# Bite_Force_System_Schematic.net
KiCad netlist of a schematic drawn in Altium Designer
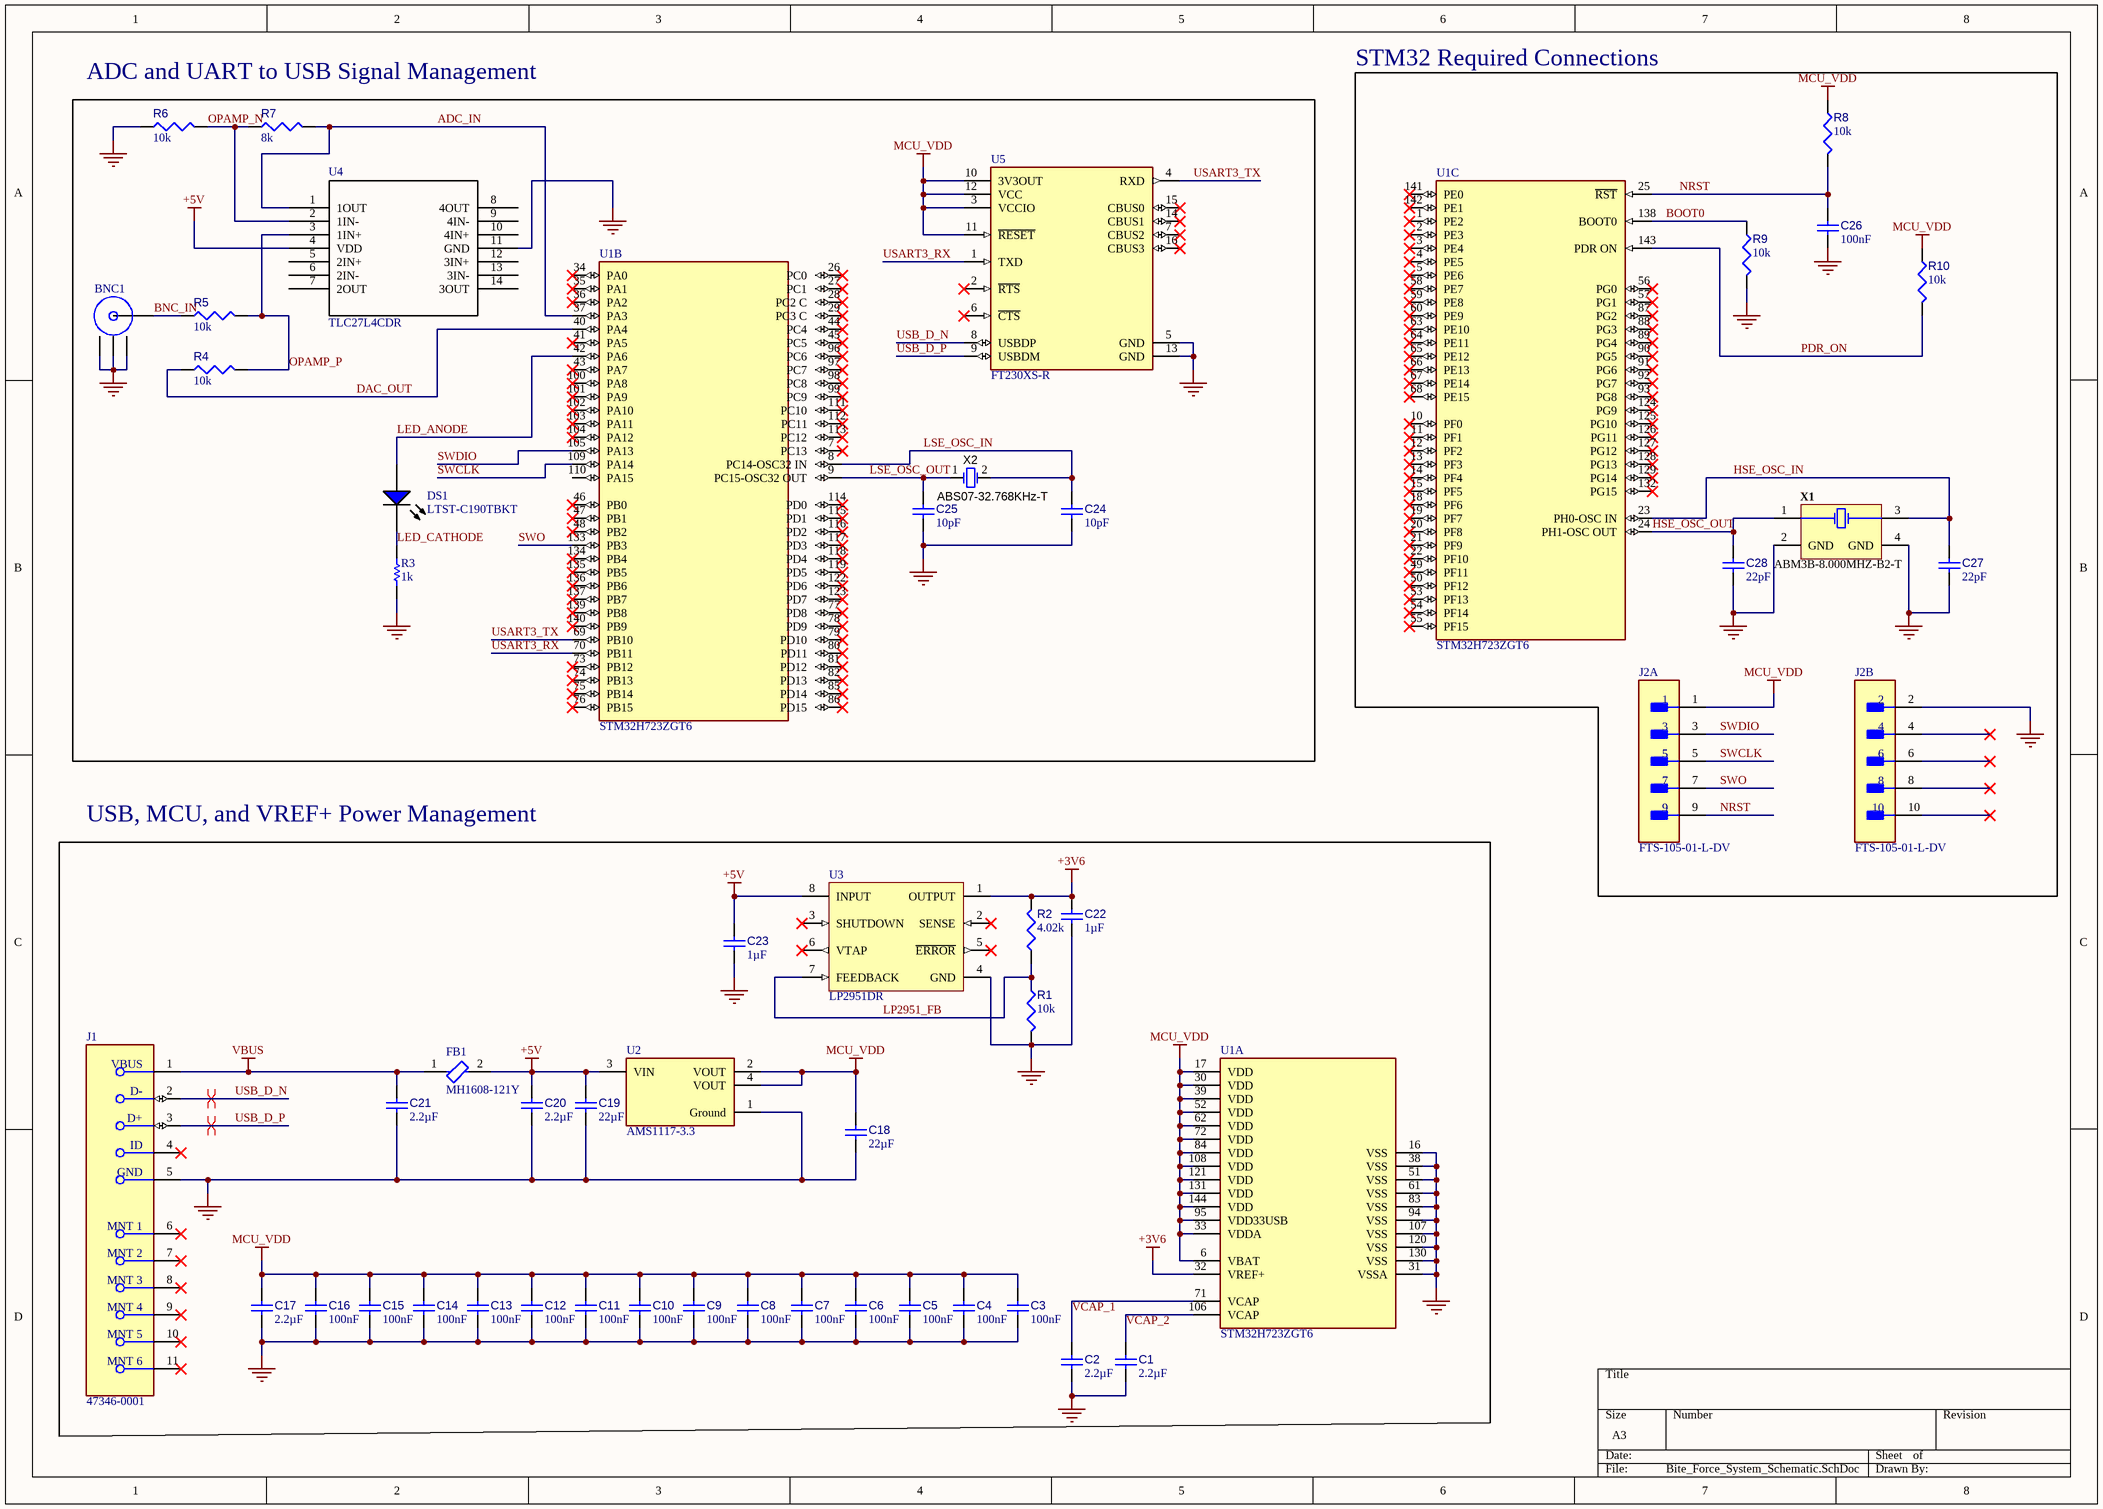
[diagram p0: Bite_Force_System_Schematic.SchDoc]

(export (version "E")
  (design (tool "Eeschema 10.0.6"))
  (components
    (comp (ref "BNC1")
      (value "KH-BNC75-3511")
      (footprint "KH-BNC75-3511-Footprint-1")
      (description "1 Inner Hole BNC Board-End Elbow 3GHz -55℃~+155℃ 75Ω 9.5mm Plugin Coaxial Connectors (RF) ROHS")
      (libsource (lib "Hayden Cao") (part "KH-BNC75-3511-Symbol-1"))
    )
    (comp (ref "C1")
      (value "2.2µF")
      (footprint "CAPC0402(1005)60_L")
      (description "Chip Capacitor, 2,2µF +/-20%, 10V, 0402, Thickness 0.6 mm")
      (fields (field (name "TOLERANCE") "10%") (field (name "Comment") "Capacitor 2,2µF +/-20% 10V 0402"))
      (libsource (lib "Hayden Cao") (part "CAP-NP-2"))
    )
    (comp (ref "C2")
      (value "2.2µF")
      (footprint "CAPC0402(1005)60_L")
      (description "Chip Capacitor, 2,2µF +/-20%, 10V, 0402, Thickness 0.6 mm")
      (fields (field (name "TOLERANCE") "10%") (field (name "Comment") "Capacitor 2,2µF +/-20% 10V 0402"))
      (libsource (lib "Hayden Cao") (part "CAP-NP-2"))
    )
    (comp (ref "C3")
      (value "100nF")
      (footprint "CAPC0402(1005)60_L")
      (description "Chip Capacitor, 100nF +/-20%, 25V, 0402, Thickness 0.6 mm")
      (fields (field (name "TOLERANCE") "10%") (field (name "Comment") "Capacitor 100nF +/-20% 25V 0402"))
      (libsource (lib "Hayden Cao") (part "CAP-NP-2"))
    )
    (comp (ref "C4")
      (value "100nF")
      (footprint "CAPC0402(1005)60_L")
      (description "Chip Capacitor, 100nF +/-20%, 25V, 0402, Thickness 0.6 mm")
      (fields (field (name "TOLERANCE") "10%") (field (name "Comment") "Capacitor 100nF +/-20% 25V 0402"))
      (libsource (lib "Hayden Cao") (part "CAP-NP-2"))
    )
    (comp (ref "C5")
      (value "100nF")
      (footprint "CAPC0402(1005)60_L")
      (description "Chip Capacitor, 100nF +/-20%, 25V, 0402, Thickness 0.6 mm")
      (fields (field (name "TOLERANCE") "10%") (field (name "Comment") "Capacitor 100nF +/-20% 25V 0402"))
      (libsource (lib "Hayden Cao") (part "CAP-NP-2"))
    )
    (comp (ref "C6")
      (value "100nF")
      (footprint "CAPC0402(1005)60_L")
      (description "Chip Capacitor, 100nF +/-20%, 25V, 0402, Thickness 0.6 mm")
      (fields (field (name "TOLERANCE") "10%") (field (name "Comment") "Capacitor 100nF +/-20% 25V 0402"))
      (libsource (lib "Hayden Cao") (part "CAP-NP-2"))
    )
    (comp (ref "C7")
      (value "100nF")
      (footprint "CAPC0402(1005)60_L")
      (description "Chip Capacitor, 100nF +/-20%, 25V, 0402, Thickness 0.6 mm")
      (fields (field (name "TOLERANCE") "10%") (field (name "Comment") "Capacitor 100nF +/-20% 25V 0402"))
      (libsource (lib "Hayden Cao") (part "CAP-NP-2"))
    )
    (comp (ref "C8")
      (value "100nF")
      (footprint "CAPC0402(1005)60_L")
      (description "Chip Capacitor, 100nF +/-20%, 25V, 0402, Thickness 0.6 mm")
      (fields (field (name "TOLERANCE") "10%") (field (name "Comment") "Capacitor 100nF +/-20% 25V 0402"))
      (libsource (lib "Hayden Cao") (part "CAP-NP-2"))
    )
    (comp (ref "C9")
      (value "100nF")
      (footprint "CAPC0402(1005)60_L")
      (description "Chip Capacitor, 100nF +/-20%, 25V, 0402, Thickness 0.6 mm")
      (fields (field (name "TOLERANCE") "10%") (field (name "Comment") "Capacitor 100nF +/-20% 25V 0402"))
      (libsource (lib "Hayden Cao") (part "CAP-NP-2"))
    )
    (comp (ref "C10")
      (value "100nF")
      (footprint "CAPC0402(1005)60_L")
      (description "Chip Capacitor, 100nF +/-20%, 25V, 0402, Thickness 0.6 mm")
      (fields (field (name "TOLERANCE") "10%") (field (name "Comment") "Capacitor 100nF +/-20% 25V 0402"))
      (libsource (lib "Hayden Cao") (part "CAP-NP-2"))
    )
    (comp (ref "C11")
      (value "100nF")
      (footprint "CAPC0402(1005)60_L")
      (description "Chip Capacitor, 100nF +/-20%, 25V, 0402, Thickness 0.6 mm")
      (fields (field (name "TOLERANCE") "10%") (field (name "Comment") "Capacitor 100nF +/-20% 25V 0402"))
      (libsource (lib "Hayden Cao") (part "CAP-NP-2"))
    )
    (comp (ref "C12")
      (value "100nF")
      (footprint "CAPC0402(1005)60_L")
      (description "Chip Capacitor, 100nF +/-20%, 25V, 0402, Thickness 0.6 mm")
      (fields (field (name "TOLERANCE") "10%") (field (name "Comment") "Capacitor 100nF +/-20% 25V 0402"))
      (libsource (lib "Hayden Cao") (part "CAP-NP-2"))
    )
    (comp (ref "C13")
      (value "100nF")
      (footprint "CAPC0402(1005)60_L")
      (description "Chip Capacitor, 100nF +/-20%, 25V, 0402, Thickness 0.6 mm")
      (fields (field (name "TOLERANCE") "10%") (field (name "Comment") "Capacitor 100nF +/-20% 25V 0402"))
      (libsource (lib "Hayden Cao") (part "CAP-NP-2"))
    )
    (comp (ref "C14")
      (value "100nF")
      (footprint "CAPC0402(1005)60_L")
      (description "Chip Capacitor, 100nF +/-20%, 25V, 0402, Thickness 0.6 mm")
      (fields (field (name "TOLERANCE") "10%") (field (name "Comment") "Capacitor 100nF +/-20% 25V 0402"))
      (libsource (lib "Hayden Cao") (part "CAP-NP-2"))
    )
    (comp (ref "C15")
      (value "100nF")
      (footprint "CAPC0402(1005)60_L")
      (description "Chip Capacitor, 100nF +/-20%, 25V, 0402, Thickness 0.6 mm")
      (fields (field (name "TOLERANCE") "10%") (field (name "Comment") "Capacitor 100nF +/-20% 25V 0402"))
      (libsource (lib "Hayden Cao") (part "CAP-NP-2"))
    )
    (comp (ref "C16")
      (value "100nF")
      (footprint "CAPC0402(1005)60_L")
      (description "Chip Capacitor, 100nF +/-20%, 25V, 0402, Thickness 0.6 mm")
      (fields (field (name "TOLERANCE") "10%") (field (name "Comment") "Capacitor 100nF +/-20% 25V 0402"))
      (libsource (lib "Hayden Cao") (part "CAP-NP-2"))
    )
    (comp (ref "C17")
      (value "2.2µF")
      (footprint "CAPC0402(1005)60_L")
      (description "Chip Capacitor, 2,2µF +/-20%, 10V, 0402, Thickness 0.6 mm")
      (fields (field (name "TOLERANCE") "10%") (field (name "Comment") "Capacitor 2,2µF +/-20% 10V 0402"))
      (libsource (lib "Hayden Cao") (part "CAP-NP-2"))
    )
    (comp (ref "C18")
      (value "22µF")
      (footprint "CAPC0805(2012)145_L")
      (description "Chip Capacitor, 22µF +/-40%, 16V, 0805, Thickness 1.45 mm")
      (fields (field (name "TOLERANCE") "5%") (field (name "Comment") "Capacitor 22µF +/-40% 16V 0805"))
      (libsource (lib "Hayden Cao") (part "CAP-NP-2"))
    )
    (comp (ref "C19")
      (value "22µF")
      (footprint "CAPC0805(2012)145_L")
      (description "Chip Capacitor, 22µF +/-40%, 16V, 0805, Thickness 1.45 mm")
      (fields (field (name "TOLERANCE") "5%") (field (name "Comment") "Capacitor 22µF +/-40% 16V 0805"))
      (libsource (lib "Hayden Cao") (part "CAP-NP-2"))
    )
    (comp (ref "C20")
      (value "2.2µF")
      (footprint "CAPC0402(1005)60_L")
      (description "Chip Capacitor, 2,2µF +/-20%, 10V, 0402, Thickness 0.6 mm")
      (fields (field (name "TOLERANCE") "10%") (field (name "Comment") "Capacitor 2,2µF +/-20% 10V 0402"))
      (libsource (lib "Hayden Cao") (part "CAP-NP-2"))
    )
    (comp (ref "C21")
      (value "2.2µF")
      (footprint "CAPC0402(1005)60_L")
      (description "Chip Capacitor, 2,2µF +/-20%, 10V, 0402, Thickness 0.6 mm")
      (fields (field (name "TOLERANCE") "10%") (field (name "Comment") "Capacitor 2,2µF +/-20% 10V 0402"))
      (libsource (lib "Hayden Cao") (part "CAP-NP-2"))
    )
    (comp (ref "C22")
      (value "1µF")
      (footprint "CAPC1608X90X35ML15T15")
      (description "Chip Capacitor, 1 uF, +/- 10%, 16 V, 0603 (1608 Metric)")
      (fields (field (name "TOLERANCE") "10%") (field (name "Comment") "Capacitor 1uF +/- 10% 16V 0603"))
      (libsource (lib "Hayden Cao") (part "CAP-NP-2"))
    )
    (comp (ref "C23")
      (value "1µF")
      (footprint "CAPC1608X90X35ML15T15")
      (description "Chip Capacitor, 1 uF, +/- 10%, 16 V, 0603 (1608 Metric)")
      (fields (field (name "TOLERANCE") "10%") (field (name "Comment") "Capacitor 1uF +/- 10% 16V 0603"))
      (libsource (lib "Hayden Cao") (part "CAP-NP-2"))
    )
    (comp (ref "C24")
      (value "10pF")
      (footprint "CAPC1005X55X25ML05T05")
      (description "Chip Capacitor, 10 pF, +/- 5%, 50 V, 0402 (1005 Metric)")
      (fields (field (name "TOLERANCE") "5%") (field (name "Comment") "Capacitor 10 pF +/- 5% 50 V 0402"))
      (libsource (lib "Hayden Cao") (part "CAP-NP-2"))
    )
    (comp (ref "C25")
      (value "10pF")
      (footprint "CAPC1005X55X25ML05T05")
      (description "Chip Capacitor, 10 pF, +/- 5%, 50 V, 0402 (1005 Metric)")
      (fields (field (name "TOLERANCE") "5%") (field (name "Comment") "Capacitor 10 pF +/- 5% 50 V 0402"))
      (libsource (lib "Hayden Cao") (part "CAP-NP-2"))
    )
    (comp (ref "C26")
      (value "100nF")
      (footprint "CAPC0402(1005)60_L")
      (description "Chip Capacitor, 100nF +/-20%, 25V, 0402, Thickness 0.6 mm")
      (fields (field (name "TOLERANCE") "10%") (field (name "Comment") "Capacitor 100nF +/-20% 25V 0402"))
      (libsource (lib "Hayden Cao") (part "CAP-NP-2"))
    )
    (comp (ref "C27")
      (value "22pF")
      (footprint "CAPC0402(1005)60_L")
      (description "Chip Capacitor, 22pF +/-10%, 50V, 0402, Thickness 0.6 mm")
      (fields (field (name "TOLERANCE") "10%") (field (name "Comment") "Capacitor 22pF +/-10% 50V 0402"))
      (libsource (lib "Hayden Cao") (part "CAP-NP-2"))
    )
    (comp (ref "C28")
      (value "22pF")
      (footprint "CAPC0402(1005)60_L")
      (description "Chip Capacitor, 22pF +/-10%, 50V, 0402, Thickness 0.6 mm")
      (fields (field (name "TOLERANCE") "10%") (field (name "Comment") "Capacitor 22pF +/-10% 50V 0402"))
      (libsource (lib "Hayden Cao") (part "CAP-NP-2"))
    )
    (comp (ref "DS1")
      (value "LTST-C190TBKT")
      (footprint "LTST-C190TBKT-2_V")
      (description "LED Uni-Color Blue, 76 mW, 20 mA, -20 to 80 degC, 2-Pin SMD, RoHS, Tape and Reel")
      (fields (field (name "MANUFACTURER") "Lite-On"))
      (libsource (lib "Hayden Cao") (part "LED-BLUE-AK-2"))
    )
    (comp (ref "FB1")
      (value "MH1608-121Y")
      (footprint "FP-MH1608-MFG")
      (description "Ferrite Chip, 1 Function(s), 2A, 2 Pin(s)")
      (libsource (lib "Hayden Cao") (part "5f30dd21d616792df468990f7003faa"))
    )
    (comp (ref "J1")
      (value "47346-0001")
      (footprint "FP-473460001-MFG")
      (description "USB Connector, 5 Contact(s), Female, Right Angle, Surface Mount Terminal, Locking, Receptacle")
      (libsource (lib "Hayden Cao") (part "53ae1f1d9b557310b43ca686e5bb76a"))
    )
    (comp (ref "J2")
      (value "FTS-105-01-L-DV")
      (footprint "FP-FTS-105-01-L-DV-MFG")
      (libsource (lib "Hayden Cao") (part "26e02f21047a3522f1f1d80f6153eae"))
    )
    (comp (ref "R1")
      (value "10k")
      (footprint "RESC0402(1005)_L")
      (description "Chip Resistor, 10 kOhms, +/-1 %, 63 mW, -55 to 125 degC, 0402")
      (fields (field (name "POWER") "63mW") (field (name "TOLERANCE") "1%"))
      (libsource (lib "Hayden Cao") (part "RES-2"))
    )
    (comp (ref "R2")
      (value "4.02k")
      (footprint "RESC0402(1005)_L")
      (description "Chip Resistor, 4,02 kOhms, +/-1 %, 63 mW, -55 to 155 degC, 0402")
      (fields (field (name "POWER") "63mW") (field (name "TOLERANCE") "1%"))
      (libsource (lib "Hayden Cao") (part "RES-2"))
    )
    (comp (ref "R3")
      (value "1k")
      (footprint "RESC3116X70X50ML13T20")
      (description "Chip Resistor, 1 KOhm, +/- 1%, 0.25 W, -55 to 155 degC, 1206 (3216 Metric)")
      (fields (field (name "TOLERANCE") "1%") (field (name "POWER") "250mW"))
      (libsource (lib "") (part "RES-2_1"))
    )
    (comp (ref "R4")
      (value "10k")
      (footprint "RESC0402(1005)_L")
      (description "Chip Resistor, 10 kOhms, +/-1 %, 63 mW, -55 to 125 degC, 0402")
      (fields (field (name "POWER") "63mW") (field (name "TOLERANCE") "1%"))
      (libsource (lib "Hayden Cao") (part "RES-2"))
    )
    (comp (ref "R5")
      (value "10k")
      (footprint "RESC0402(1005)_L")
      (description "Chip Resistor, 10 kOhms, +/-1 %, 63 mW, -55 to 125 degC, 0402")
      (fields (field (name "POWER") "63mW") (field (name "TOLERANCE") "1%"))
      (libsource (lib "Hayden Cao") (part "RES-2"))
    )
    (comp (ref "R6")
      (value "10k")
      (footprint "RESC0402(1005)_L")
      (description "Chip Resistor, 10 kOhms, +/-1 %, 63 mW, -55 to 125 degC, 0402")
      (fields (field (name "POWER") "63mW") (field (name "TOLERANCE") "1%"))
      (libsource (lib "Hayden Cao") (part "RES-2"))
    )
    (comp (ref "R7")
      (value "8k")
      (footprint "RT0603BRE078KL-Footprint-1")
      (description "Fixed Resistor")
      (fields (field (name "TOLERANCE") "0.1%") (field (name "POWER") "100mW"))
      (libsource (lib "Hayden Cao") (part "RES-2"))
    )
    (comp (ref "R8")
      (value "10k")
      (footprint "RESC0402(1005)_L")
      (description "Chip Resistor, 10 kOhms, +/-1 %, 63 mW, -55 to 125 degC, 0402")
      (fields (field (name "POWER") "63mW") (field (name "TOLERANCE") "1%"))
      (libsource (lib "Hayden Cao") (part "RES-2"))
    )
    (comp (ref "R9")
      (value "10k")
      (footprint "RESC0402(1005)_L")
      (description "Chip Resistor, 10 kOhms, +/-1 %, 63 mW, -55 to 125 degC, 0402")
      (fields (field (name "POWER") "63mW") (field (name "TOLERANCE") "1%"))
      (libsource (lib "Hayden Cao") (part "RES-2"))
    )
    (comp (ref "R10")
      (value "10k")
      (footprint "RESC0402(1005)_L")
      (description "Chip Resistor, 10 kOhms, +/-1 %, 63 mW, -55 to 125 degC, 0402")
      (fields (field (name "POWER") "63mW") (field (name "TOLERANCE") "1%"))
      (libsource (lib "Hayden Cao") (part "RES-2"))
    )
    (comp (ref "U1")
      (value "STM32H723ZGT6")
      (footprint "FP-LQFP144-1A-MFG")
      (description "RISC Microcontroller, 32-Bit, FLASH, CORTEX-M7 CPU, 550MHz, CMOS, PQFP144")
      (libsource (lib "Hayden Cao") (part "099c9e622ff36f7eb897f9cba6d1f51"))
    )
    (comp (ref "U2")
      (value "AMS1117-3.3")
      (footprint "FP-AMS1117-IPC_B")
      (description "Fixed Positive LDO Regulator, 3.3V, 1.3V Dropout, PDSO3")
      (libsource (lib "Hayden Cao") (part "8bdbb5f8e77002000e30dd2845d0354"))
    )
    (comp (ref "U3")
      (value "LP2951DR")
      (footprint "D0008A_L")
      (description "Adjustable Positive LDO Regulator, 1.235V Min, 30V Max, 0.6V Dropout, BIPolar, PDSO8")
      (libsource (lib "Hayden Cao") (part "TI-LP2951-D8"))
    )
    (comp (ref "U4")
      (value "TLC27L4CDR")
      (footprint "TLC27L4CDR-Footprint-1")
      (description "Operational Amplifier, 4 Func, 12000uV Offset-Max, CMOS, PDSO14")
      (libsource (lib "Hayden Cao") (part "Copy of AMP-3"))
    )
    (comp (ref "U5")
      (value "FT230XS-R")
      (footprint "FP-SSOP-16-IPC_C")
      (description "Microprocessor Circuit, CMOS, PDSO16")
      (libsource (lib "Hayden Cao") (part "33f179d67b5e33a3acba2e4c59411a5"))
    )
    (comp (ref "X1")
      (value "ABM3B-8.000MHZ-B2-T")
      (footprint "ABRA-ABM3B_V")
      (description "Ceramic SMD Crystal, 8 MHz, +/- 20 ppm, 18 pF, -20 to 70 degC, 4-Pin SMD, RoHS, Tape and Reel")
      (fields (field (name "TOLERANCE") "20ppm") (field (name "MANUFACTURER") "Abracon"))
      (libsource (lib "Hayden Cao") (part "XTAL-1-3-4"))
    )
    (comp (ref "X2")
      (value "ABS07-32.768KHz-T")
      (footprint "ABRA-ABS07-2_V")
      (fields (field (name "TOLERANCE") "20ppm") (field (name "MANUFACTURER") "Abracon"))
      (libsource (lib "Hayden Cao") (part "ABRA-ABS07-2"))
    )
  )
  (nets
    (net (code "1") (name "+3V6") (class "Default")
      (node (ref "C22") (pin "1") (pinfunction "1_1") (pintype "passive"))
      (node (ref "R2") (pin "2") (pinfunction "2_2") (pintype "passive"))
      (node (ref "U1") (pin "32") (pinfunction "VREF+_32") (pintype "power_in"))
      (node (ref "U3") (pin "1") (pinfunction "OUTPUT_1") (pintype "power_in"))
    )
    (net (code "2") (name "+5V") (class "Default")
      (node (ref "C19") (pin "1") (pinfunction "1_1") (pintype "passive"))
      (node (ref "C20") (pin "1") (pinfunction "1_1") (pintype "passive"))
      (node (ref "C23") (pin "1") (pinfunction "1_1") (pintype "passive"))
      (node (ref "FB1") (pin "2") (pinfunction "2_2") (pintype "passive"))
      (node (ref "U2") (pin "3") (pinfunction "VIN_3") (pintype "power_in"))
      (node (ref "U3") (pin "8") (pinfunction "INPUT_8") (pintype "power_in"))
      (node (ref "U4") (pin "4") (pinfunction "VDD_4") (pintype "passive"))
    )
    (net (code "3") (name "/ADC_IN") (class "Default")
      (node (ref "R7") (pin "2") (pinfunction "2_2") (pintype "passive"))
      (node (ref "U1") (pin "37") (pinfunction "PA3_37") (pintype "bidirectional"))
      (node (ref "U4") (pin "1") (pinfunction "1OUT_1") (pintype "passive"))
    )
    (net (code "4") (name "/BNC_IN") (class "Default")
      (node (ref "BNC1") (pin "1") (pinfunction "1_1") (pintype "passive"))
      (node (ref "R5") (pin "1") (pinfunction "1_1") (pintype "passive"))
    )
    (net (code "5") (name "/BOOT0") (class "Default")
      (node (ref "R9") (pin "1") (pinfunction "1_1") (pintype "passive"))
      (node (ref "U1") (pin "138") (pinfunction "BOOT0_138") (pintype "input"))
    )
    (net (code "6") (name "/DAC_OUT") (class "Default")
      (node (ref "R4") (pin "1") (pinfunction "1_1") (pintype "passive"))
      (node (ref "U1") (pin "40") (pinfunction "PA4_40") (pintype "bidirectional"))
    )
    (net (code "7") (name "/HSE_OSC_IN") (class "Default")
      (node (ref "C27") (pin "2") (pinfunction "2_2") (pintype "passive"))
      (node (ref "U1") (pin "23") (pinfunction "PH0-OSC_IN_23") (pintype "bidirectional"))
      (node (ref "X1") (pin "3") (pinfunction "X2_3") (pintype "passive"))
    )
    (net (code "8") (name "/HSE_OSC_OUT") (class "Default")
      (node (ref "C28") (pin "2") (pinfunction "2_2") (pintype "passive"))
      (node (ref "U1") (pin "24") (pinfunction "PH1-OSC_OUT_24") (pintype "bidirectional"))
      (node (ref "X1") (pin "1") (pinfunction "X1_1") (pintype "passive"))
    )
    (net (code "9") (name "/LED_ANODE") (class "Default")
      (node (ref "DS1") (pin "1") (pinfunction "A_1") (pintype "passive"))
      (node (ref "U1") (pin "42") (pinfunction "PA6_42") (pintype "bidirectional"))
    )
    (net (code "10") (name "/LED_CATHODE") (class "Default")
      (node (ref "DS1") (pin "2") (pinfunction "K_2") (pintype "passive"))
      (node (ref "R3") (pin "2") (pinfunction "2_2") (pintype "passive"))
    )
    (net (code "11") (name "/LP2951_FB") (class "Default")
      (node (ref "R1") (pin "1") (pinfunction "1_1") (pintype "passive"))
      (node (ref "R2") (pin "1") (pinfunction "1_1") (pintype "passive"))
      (node (ref "U3") (pin "7") (pinfunction "FEEDBACK_7") (pintype "input"))
    )
    (net (code "12") (name "/LSE_OSC_IN") (class "Default")
      (node (ref "C24") (pin "1") (pinfunction "1_1") (pintype "passive"))
      (node (ref "U1") (pin "8") (pinfunction "PC14-OSC32_IN_8") (pintype "bidirectional"))
      (node (ref "X2") (pin "2") (pinfunction "OSC2_2") (pintype "passive"))
    )
    (net (code "13") (name "/LSE_OSC_OUT") (class "Default")
      (node (ref "C25") (pin "1") (pinfunction "1_1") (pintype "passive"))
      (node (ref "U1") (pin "9") (pinfunction "PC15-OSC32_OUT_9") (pintype "bidirectional"))
      (node (ref "X2") (pin "1") (pinfunction "OSC1_1") (pintype "passive"))
    )
    (net (code "14") (name "/NRST") (class "Default")
      (node (ref "C26") (pin "1") (pinfunction "1_1") (pintype "passive"))
      (node (ref "J2") (pin "9") (pinfunction "9_9") (pintype "passive"))
      (node (ref "R8") (pin "2") (pinfunction "2_2") (pintype "passive"))
      (node (ref "U1") (pin "25") (pinfunction "~{RST}_25") (pintype "input"))
    )
    (net (code "15") (name "/OPAMP_N") (class "Default")
      (node (ref "R6") (pin "2") (pinfunction "2_2") (pintype "passive"))
      (node (ref "R7") (pin "1") (pinfunction "1_1") (pintype "passive"))
      (node (ref "U4") (pin "2") (pinfunction "1IN-_2") (pintype "passive"))
    )
    (net (code "16") (name "/OPAMP_P") (class "Default")
      (node (ref "R4") (pin "2") (pinfunction "2_2") (pintype "passive"))
      (node (ref "R5") (pin "2") (pinfunction "2_2") (pintype "passive"))
      (node (ref "U4") (pin "3") (pinfunction "1IN+_3") (pintype "passive"))
    )
    (net (code "17") (name "/PDR_ON") (class "Default")
      (node (ref "R10") (pin "2") (pinfunction "2_2") (pintype "passive"))
      (node (ref "U1") (pin "143") (pinfunction "PDR_ON_143") (pintype "input"))
    )
    (net (code "18") (name "/SWCLK") (class "Default")
      (node (ref "J2") (pin "5") (pinfunction "5_5") (pintype "passive"))
      (node (ref "U1") (pin "109") (pinfunction "PA14_109") (pintype "bidirectional"))
    )
    (net (code "19") (name "/SWDIO") (class "Default")
      (node (ref "J2") (pin "3") (pinfunction "3_3") (pintype "passive"))
      (node (ref "U1") (pin "105") (pinfunction "PA13_105") (pintype "bidirectional"))
    )
    (net (code "20") (name "/SWO") (class "Default")
      (node (ref "J2") (pin "7") (pinfunction "7_7") (pintype "passive"))
      (node (ref "U1") (pin "133") (pinfunction "PB3_133") (pintype "bidirectional"))
    )
    (net (code "21") (name "/USART3_RX") (class "Default")
      (node (ref "U1") (pin "70") (pinfunction "PB11_70") (pintype "bidirectional"))
      (node (ref "U5") (pin "1") (pinfunction "TXD_1") (pintype "input"))
    )
    (net (code "22") (name "/USART3_TX") (class "Default")
      (node (ref "U1") (pin "69") (pinfunction "PB10_69") (pintype "bidirectional"))
      (node (ref "U5") (pin "4") (pinfunction "RXD_4") (pintype "output"))
    )
    (net (code "23") (name "/USB_D_N") (class "Default")
      (node (ref "J1") (pin "2") (pinfunction "D-_2") (pintype "bidirectional"))
      (node (ref "U5") (pin "8") (pinfunction "USBDP_8") (pintype "bidirectional"))
    )
    (net (code "24") (name "/USB_D_P") (class "Default")
      (node (ref "J1") (pin "3") (pinfunction "D+_3") (pintype "bidirectional"))
      (node (ref "U5") (pin "9") (pinfunction "USBDM_9") (pintype "bidirectional"))
    )
    (net (code "25") (name "/VCAP_1") (class "Default")
      (node (ref "C2") (pin "1") (pinfunction "1_1") (pintype "passive"))
      (node (ref "U1") (pin "71") (pinfunction "VCAP_71") (pintype "power_in"))
    )
    (net (code "26") (name "/VCAP_2") (class "Default")
      (node (ref "C1") (pin "1") (pinfunction "1_1") (pintype "passive"))
      (node (ref "U1") (pin "106") (pinfunction "VCAP_106") (pintype "power_in"))
    )
    (net (code "27") (name "GND") (class "Default")
      (node (ref "BNC1") (pin "2") (pinfunction "2_2") (pintype "passive"))
      (node (ref "BNC1") (pin "3") (pinfunction "3_3") (pintype "passive"))
      (node (ref "BNC1") (pin "4") (pinfunction "4_4") (pintype "passive"))
      (node (ref "C1") (pin "2") (pinfunction "2_2") (pintype "passive"))
      (node (ref "C10") (pin "2") (pinfunction "2_2") (pintype "passive"))
      (node (ref "C11") (pin "2") (pinfunction "2_2") (pintype "passive"))
      (node (ref "C12") (pin "2") (pinfunction "2_2") (pintype "passive"))
      (node (ref "C13") (pin "2") (pinfunction "2_2") (pintype "passive"))
      (node (ref "C14") (pin "2") (pinfunction "2_2") (pintype "passive"))
      (node (ref "C15") (pin "2") (pinfunction "2_2") (pintype "passive"))
      (node (ref "C16") (pin "2") (pinfunction "2_2") (pintype "passive"))
      (node (ref "C17") (pin "2") (pinfunction "2_2") (pintype "passive"))
      (node (ref "C18") (pin "2") (pinfunction "2_2") (pintype "passive"))
      (node (ref "C19") (pin "2") (pinfunction "2_2") (pintype "passive"))
      (node (ref "C2") (pin "2") (pinfunction "2_2") (pintype "passive"))
      (node (ref "C20") (pin "2") (pinfunction "2_2") (pintype "passive"))
      (node (ref "C21") (pin "2") (pinfunction "2_2") (pintype "passive"))
      (node (ref "C22") (pin "2") (pinfunction "2_2") (pintype "passive"))
      (node (ref "C23") (pin "2") (pinfunction "2_2") (pintype "passive"))
      (node (ref "C24") (pin "2") (pinfunction "2_2") (pintype "passive"))
      (node (ref "C25") (pin "2") (pinfunction "2_2") (pintype "passive"))
      (node (ref "C26") (pin "2") (pinfunction "2_2") (pintype "passive"))
      (node (ref "C27") (pin "1") (pinfunction "1_1") (pintype "passive"))
      (node (ref "C28") (pin "1") (pinfunction "1_1") (pintype "passive"))
      (node (ref "C3") (pin "2") (pinfunction "2_2") (pintype "passive"))
      (node (ref "C4") (pin "2") (pinfunction "2_2") (pintype "passive"))
      (node (ref "C5") (pin "2") (pinfunction "2_2") (pintype "passive"))
      (node (ref "C6") (pin "2") (pinfunction "2_2") (pintype "passive"))
      (node (ref "C7") (pin "2") (pinfunction "2_2") (pintype "passive"))
      (node (ref "C8") (pin "2") (pinfunction "2_2") (pintype "passive"))
      (node (ref "C9") (pin "2") (pinfunction "2_2") (pintype "passive"))
      (node (ref "J1") (pin "5") (pinfunction "GND_5") (pintype "power_in"))
      (node (ref "J2") (pin "2") (pinfunction "2_2") (pintype "passive"))
      (node (ref "R1") (pin "2") (pinfunction "2_2") (pintype "passive"))
      (node (ref "R3") (pin "1") (pinfunction "1_1") (pintype "passive"))
      (node (ref "R6") (pin "1") (pinfunction "1_1") (pintype "passive"))
      (node (ref "R9") (pin "2") (pinfunction "2_2") (pintype "passive"))
      (node (ref "U1") (pin "107") (pinfunction "VSS_107") (pintype "power_in"))
      (node (ref "U1") (pin "120") (pinfunction "VSS_120") (pintype "power_in"))
      (node (ref "U1") (pin "130") (pinfunction "VSS_130") (pintype "power_in"))
      (node (ref "U1") (pin "16") (pinfunction "VSS_16") (pintype "power_in"))
      (node (ref "U1") (pin "31") (pinfunction "VSSA_31") (pintype "power_in"))
      (node (ref "U1") (pin "38") (pinfunction "VSS_38") (pintype "power_in"))
      (node (ref "U1") (pin "51") (pinfunction "VSS_51") (pintype "power_in"))
      (node (ref "U1") (pin "61") (pinfunction "VSS_61") (pintype "power_in"))
      (node (ref "U1") (pin "83") (pinfunction "VSS_83") (pintype "power_in"))
      (node (ref "U1") (pin "94") (pinfunction "VSS_94") (pintype "power_in"))
      (node (ref "U2") (pin "1") (pinfunction "Ground_1") (pintype "power_in"))
      (node (ref "U3") (pin "4") (pinfunction "GND_4") (pintype "power_in"))
      (node (ref "U4") (pin "11") (pinfunction "GND_11") (pintype "passive"))
      (node (ref "U5") (pin "13") (pinfunction "GND_13") (pintype "power_in"))
      (node (ref "U5") (pin "5") (pinfunction "GND_5") (pintype "power_in"))
      (node (ref "X1") (pin "2") (pinfunction "GND_2") (pintype "power_in"))
      (node (ref "X1") (pin "4") (pinfunction "GND_4") (pintype "power_in"))
    )
    (net (code "28") (name "MCU_VDD") (class "Default")
      (node (ref "C10") (pin "1") (pinfunction "1_1") (pintype "passive"))
      (node (ref "C11") (pin "1") (pinfunction "1_1") (pintype "passive"))
      (node (ref "C12") (pin "1") (pinfunction "1_1") (pintype "passive"))
      (node (ref "C13") (pin "1") (pinfunction "1_1") (pintype "passive"))
      (node (ref "C14") (pin "1") (pinfunction "1_1") (pintype "passive"))
      (node (ref "C15") (pin "1") (pinfunction "1_1") (pintype "passive"))
      (node (ref "C16") (pin "1") (pinfunction "1_1") (pintype "passive"))
      (node (ref "C17") (pin "1") (pinfunction "1_1") (pintype "passive"))
      (node (ref "C18") (pin "1") (pinfunction "1_1") (pintype "passive"))
      (node (ref "C3") (pin "1") (pinfunction "1_1") (pintype "passive"))
      (node (ref "C4") (pin "1") (pinfunction "1_1") (pintype "passive"))
      (node (ref "C5") (pin "1") (pinfunction "1_1") (pintype "passive"))
      (node (ref "C6") (pin "1") (pinfunction "1_1") (pintype "passive"))
      (node (ref "C7") (pin "1") (pinfunction "1_1") (pintype "passive"))
      (node (ref "C8") (pin "1") (pinfunction "1_1") (pintype "passive"))
      (node (ref "C9") (pin "1") (pinfunction "1_1") (pintype "passive"))
      (node (ref "J2") (pin "1") (pinfunction "1_1") (pintype "passive"))
      (node (ref "R10") (pin "1") (pinfunction "1_1") (pintype "passive"))
      (node (ref "R8") (pin "1") (pinfunction "1_1") (pintype "passive"))
      (node (ref "U1") (pin "108") (pinfunction "VDD_108") (pintype "power_in"))
      (node (ref "U1") (pin "121") (pinfunction "VDD_121") (pintype "power_in"))
      (node (ref "U1") (pin "131") (pinfunction "VDD_131") (pintype "power_in"))
      (node (ref "U1") (pin "144") (pinfunction "VDD_144") (pintype "power_in"))
      (node (ref "U1") (pin "17") (pinfunction "VDD_17") (pintype "power_in"))
      (node (ref "U1") (pin "30") (pinfunction "VDD_30") (pintype "power_in"))
      (node (ref "U1") (pin "33") (pinfunction "VDDA_33") (pintype "power_in"))
      (node (ref "U1") (pin "39") (pinfunction "VDD_39") (pintype "power_in"))
      (node (ref "U1") (pin "52") (pinfunction "VDD_52") (pintype "power_in"))
      (node (ref "U1") (pin "6") (pinfunction "VBAT_6") (pintype "power_in"))
      (node (ref "U1") (pin "62") (pinfunction "VDD_62") (pintype "power_in"))
      (node (ref "U1") (pin "72") (pinfunction "VDD_72") (pintype "power_in"))
      (node (ref "U1") (pin "84") (pinfunction "VDD_84") (pintype "power_in"))
      (node (ref "U1") (pin "95") (pinfunction "VDD33USB_95") (pintype "power_in"))
      (node (ref "U2") (pin "2") (pinfunction "VOUT_2") (pintype "passive"))
      (node (ref "U2") (pin "4") (pinfunction "VOUT_4") (pintype "passive"))
      (node (ref "U5") (pin "10") (pinfunction "3V3OUT_10") (pintype "power_in"))
      (node (ref "U5") (pin "11") (pinfunction "~{RESET}_11") (pintype "input"))
      (node (ref "U5") (pin "12") (pinfunction "VCC_12") (pintype "power_in"))
      (node (ref "U5") (pin "3") (pinfunction "VCCIO_3") (pintype "power_in"))
    )
    (net (code "29") (name "VBUS") (class "Default")
      (node (ref "C21") (pin "1") (pinfunction "1_1") (pintype "passive"))
      (node (ref "FB1") (pin "1") (pinfunction "1_1") (pintype "passive"))
      (node (ref "J1") (pin "1") (pinfunction "VBUS_1") (pintype "power_in"))
    )
    (net (code "30") (name "unconnected-(J1-ID-Pad4)") (class "Default")
      (node (ref "J1") (pin "4") (pinfunction "ID_4") (pintype "passive+no_connect"))
    )
    (net (code "31") (name "unconnected-(J1-MNT_1-Pad6)") (class "Default")
      (node (ref "J1") (pin "6") (pinfunction "MNT_1_6") (pintype "passive+no_connect"))
    )
    (net (code "32") (name "unconnected-(J1-MNT_2-Pad7)") (class "Default")
      (node (ref "J1") (pin "7") (pinfunction "MNT_2_7") (pintype "passive+no_connect"))
    )
    (net (code "33") (name "unconnected-(J1-MNT_3-Pad8)") (class "Default")
      (node (ref "J1") (pin "8") (pinfunction "MNT_3_8") (pintype "passive+no_connect"))
    )
    (net (code "34") (name "unconnected-(J1-MNT_4-Pad9)") (class "Default")
      (node (ref "J1") (pin "9") (pinfunction "MNT_4_9") (pintype "passive+no_connect"))
    )
    (net (code "35") (name "unconnected-(J1-MNT_5-Pad10)") (class "Default")
      (node (ref "J1") (pin "10") (pinfunction "MNT_5_10") (pintype "passive+no_connect"))
    )
    (net (code "36") (name "unconnected-(J1-MNT_6-Pad11)") (class "Default")
      (node (ref "J1") (pin "11") (pinfunction "MNT_6_11") (pintype "passive+no_connect"))
    )
    (net (code "37") (name "unconnected-(J2-Pad4)") (class "Default")
      (node (ref "J2") (pin "4") (pinfunction "4_4") (pintype "passive+no_connect"))
    )
    (net (code "38") (name "unconnected-(J2-Pad6)") (class "Default")
      (node (ref "J2") (pin "6") (pinfunction "6_6") (pintype "passive+no_connect"))
    )
    (net (code "39") (name "unconnected-(J2-Pad8)") (class "Default")
      (node (ref "J2") (pin "8") (pinfunction "8_8") (pintype "passive+no_connect"))
    )
    (net (code "40") (name "unconnected-(J2-Pad10)") (class "Default")
      (node (ref "J2") (pin "10") (pinfunction "10_10") (pintype "passive+no_connect"))
    )
    (net (code "41") (name "unconnected-(U1B-PA0-Pad34)") (class "Default")
      (node (ref "U1") (pin "34") (pinfunction "PA0_34") (pintype "bidirectional+no_connect"))
    )
    (net (code "42") (name "unconnected-(U1B-PA1-Pad35)") (class "Default")
      (node (ref "U1") (pin "35") (pinfunction "PA1_35") (pintype "bidirectional+no_connect"))
    )
    (net (code "43") (name "unconnected-(U1B-PA2-Pad36)") (class "Default")
      (node (ref "U1") (pin "36") (pinfunction "PA2_36") (pintype "bidirectional+no_connect"))
    )
    (net (code "44") (name "unconnected-(U1B-PA5-Pad41)") (class "Default")
      (node (ref "U1") (pin "41") (pinfunction "PA5_41") (pintype "bidirectional+no_connect"))
    )
    (net (code "45") (name "unconnected-(U1B-PA7-Pad43)") (class "Default")
      (node (ref "U1") (pin "43") (pinfunction "PA7_43") (pintype "bidirectional+no_connect"))
    )
    (net (code "46") (name "unconnected-(U1B-PA8-Pad100)") (class "Default")
      (node (ref "U1") (pin "100") (pinfunction "PA8_100") (pintype "bidirectional+no_connect"))
    )
    (net (code "47") (name "unconnected-(U1B-PA9-Pad101)") (class "Default")
      (node (ref "U1") (pin "101") (pinfunction "PA9_101") (pintype "bidirectional+no_connect"))
    )
    (net (code "48") (name "unconnected-(U1B-PA10-Pad102)") (class "Default")
      (node (ref "U1") (pin "102") (pinfunction "PA10_102") (pintype "bidirectional+no_connect"))
    )
    (net (code "49") (name "unconnected-(U1B-PA11-Pad103)") (class "Default")
      (node (ref "U1") (pin "103") (pinfunction "PA11_103") (pintype "bidirectional+no_connect"))
    )
    (net (code "50") (name "unconnected-(U1B-PA12-Pad104)") (class "Default")
      (node (ref "U1") (pin "104") (pinfunction "PA12_104") (pintype "bidirectional+no_connect"))
    )
    (net (code "51") (name "unconnected-(U1B-PA15-Pad110)") (class "Default")
      (node (ref "U1") (pin "110") (pinfunction "PA15_110") (pintype "bidirectional"))
    )
    (net (code "52") (name "unconnected-(U1B-PB0-Pad46)") (class "Default")
      (node (ref "U1") (pin "46") (pinfunction "PB0_46") (pintype "bidirectional+no_connect"))
    )
    (net (code "53") (name "unconnected-(U1B-PB1-Pad47)") (class "Default")
      (node (ref "U1") (pin "47") (pinfunction "PB1_47") (pintype "bidirectional+no_connect"))
    )
    (net (code "54") (name "unconnected-(U1B-PB2-Pad48)") (class "Default")
      (node (ref "U1") (pin "48") (pinfunction "PB2_48") (pintype "bidirectional+no_connect"))
    )
    (net (code "55") (name "unconnected-(U1B-PB4-Pad134)") (class "Default")
      (node (ref "U1") (pin "134") (pinfunction "PB4_134") (pintype "bidirectional+no_connect"))
    )
    (net (code "56") (name "unconnected-(U1B-PB5-Pad135)") (class "Default")
      (node (ref "U1") (pin "135") (pinfunction "PB5_135") (pintype "bidirectional+no_connect"))
    )
    (net (code "57") (name "unconnected-(U1B-PB6-Pad136)") (class "Default")
      (node (ref "U1") (pin "136") (pinfunction "PB6_136") (pintype "bidirectional+no_connect"))
    )
    (net (code "58") (name "unconnected-(U1B-PB7-Pad137)") (class "Default")
      (node (ref "U1") (pin "137") (pinfunction "PB7_137") (pintype "bidirectional+no_connect"))
    )
    (net (code "59") (name "unconnected-(U1B-PB8-Pad139)") (class "Default")
      (node (ref "U1") (pin "139") (pinfunction "PB8_139") (pintype "bidirectional+no_connect"))
    )
    (net (code "60") (name "unconnected-(U1B-PB9-Pad140)") (class "Default")
      (node (ref "U1") (pin "140") (pinfunction "PB9_140") (pintype "bidirectional+no_connect"))
    )
    (net (code "61") (name "unconnected-(U1B-PB12-Pad73)") (class "Default")
      (node (ref "U1") (pin "73") (pinfunction "PB12_73") (pintype "bidirectional+no_connect"))
    )
    (net (code "62") (name "unconnected-(U1B-PB13-Pad74)") (class "Default")
      (node (ref "U1") (pin "74") (pinfunction "PB13_74") (pintype "bidirectional+no_connect"))
    )
    (net (code "63") (name "unconnected-(U1B-PB14-Pad75)") (class "Default")
      (node (ref "U1") (pin "75") (pinfunction "PB14_75") (pintype "bidirectional+no_connect"))
    )
    (net (code "64") (name "unconnected-(U1B-PB15-Pad76)") (class "Default")
      (node (ref "U1") (pin "76") (pinfunction "PB15_76") (pintype "bidirectional+no_connect"))
    )
    (net (code "65") (name "unconnected-(U1B-PC0-Pad26)") (class "Default")
      (node (ref "U1") (pin "26") (pinfunction "PC0_26") (pintype "bidirectional+no_connect"))
    )
    (net (code "66") (name "unconnected-(U1B-PC1-Pad27)") (class "Default")
      (node (ref "U1") (pin "27") (pinfunction "PC1_27") (pintype "bidirectional+no_connect"))
    )
    (net (code "67") (name "unconnected-(U1B-PC2_C-Pad28)") (class "Default")
      (node (ref "U1") (pin "28") (pinfunction "PC2_C_28") (pintype "bidirectional+no_connect"))
    )
    (net (code "68") (name "unconnected-(U1B-PC3_C-Pad29)") (class "Default")
      (node (ref "U1") (pin "29") (pinfunction "PC3_C_29") (pintype "bidirectional+no_connect"))
    )
    (net (code "69") (name "unconnected-(U1B-PC4-Pad44)") (class "Default")
      (node (ref "U1") (pin "44") (pinfunction "PC4_44") (pintype "bidirectional+no_connect"))
    )
    (net (code "70") (name "unconnected-(U1B-PC5-Pad45)") (class "Default")
      (node (ref "U1") (pin "45") (pinfunction "PC5_45") (pintype "bidirectional+no_connect"))
    )
    (net (code "71") (name "unconnected-(U1B-PC6-Pad96)") (class "Default")
      (node (ref "U1") (pin "96") (pinfunction "PC6_96") (pintype "bidirectional+no_connect"))
    )
    (net (code "72") (name "unconnected-(U1B-PC7-Pad97)") (class "Default")
      (node (ref "U1") (pin "97") (pinfunction "PC7_97") (pintype "bidirectional+no_connect"))
    )
    (net (code "73") (name "unconnected-(U1B-PC8-Pad98)") (class "Default")
      (node (ref "U1") (pin "98") (pinfunction "PC8_98") (pintype "bidirectional+no_connect"))
    )
    (net (code "74") (name "unconnected-(U1B-PC9-Pad99)") (class "Default")
      (node (ref "U1") (pin "99") (pinfunction "PC9_99") (pintype "bidirectional+no_connect"))
    )
    (net (code "75") (name "unconnected-(U1B-PC10-Pad111)") (class "Default")
      (node (ref "U1") (pin "111") (pinfunction "PC10_111") (pintype "bidirectional+no_connect"))
    )
    (net (code "76") (name "unconnected-(U1B-PC11-Pad112)") (class "Default")
      (node (ref "U1") (pin "112") (pinfunction "PC11_112") (pintype "bidirectional+no_connect"))
    )
    (net (code "77") (name "unconnected-(U1B-PC12-Pad113)") (class "Default")
      (node (ref "U1") (pin "113") (pinfunction "PC12_113") (pintype "bidirectional+no_connect"))
    )
    (net (code "78") (name "unconnected-(U1B-PC13-Pad7)") (class "Default")
      (node (ref "U1") (pin "7") (pinfunction "PC13_7") (pintype "bidirectional+no_connect"))
    )
    (net (code "79") (name "unconnected-(U1B-PD0-Pad114)") (class "Default")
      (node (ref "U1") (pin "114") (pinfunction "PD0_114") (pintype "bidirectional+no_connect"))
    )
    (net (code "80") (name "unconnected-(U1B-PD1-Pad115)") (class "Default")
      (node (ref "U1") (pin "115") (pinfunction "PD1_115") (pintype "bidirectional+no_connect"))
    )
    (net (code "81") (name "unconnected-(U1B-PD2-Pad116)") (class "Default")
      (node (ref "U1") (pin "116") (pinfunction "PD2_116") (pintype "bidirectional+no_connect"))
    )
    (net (code "82") (name "unconnected-(U1B-PD3-Pad117)") (class "Default")
      (node (ref "U1") (pin "117") (pinfunction "PD3_117") (pintype "bidirectional+no_connect"))
    )
    (net (code "83") (name "unconnected-(U1B-PD4-Pad118)") (class "Default")
      (node (ref "U1") (pin "118") (pinfunction "PD4_118") (pintype "bidirectional+no_connect"))
    )
    (net (code "84") (name "unconnected-(U1B-PD5-Pad119)") (class "Default")
      (node (ref "U1") (pin "119") (pinfunction "PD5_119") (pintype "bidirectional+no_connect"))
    )
    (net (code "85") (name "unconnected-(U1B-PD6-Pad122)") (class "Default")
      (node (ref "U1") (pin "122") (pinfunction "PD6_122") (pintype "bidirectional+no_connect"))
    )
    (net (code "86") (name "unconnected-(U1B-PD7-Pad123)") (class "Default")
      (node (ref "U1") (pin "123") (pinfunction "PD7_123") (pintype "bidirectional+no_connect"))
    )
    (net (code "87") (name "unconnected-(U1B-PD8-Pad77)") (class "Default")
      (node (ref "U1") (pin "77") (pinfunction "PD8_77") (pintype "bidirectional+no_connect"))
    )
    (net (code "88") (name "unconnected-(U1B-PD9-Pad78)") (class "Default")
      (node (ref "U1") (pin "78") (pinfunction "PD9_78") (pintype "bidirectional+no_connect"))
    )
    (net (code "89") (name "unconnected-(U1B-PD10-Pad79)") (class "Default")
      (node (ref "U1") (pin "79") (pinfunction "PD10_79") (pintype "bidirectional+no_connect"))
    )
    (net (code "90") (name "unconnected-(U1B-PD11-Pad80)") (class "Default")
      (node (ref "U1") (pin "80") (pinfunction "PD11_80") (pintype "bidirectional+no_connect"))
    )
    (net (code "91") (name "unconnected-(U1B-PD12-Pad81)") (class "Default")
      (node (ref "U1") (pin "81") (pinfunction "PD12_81") (pintype "bidirectional+no_connect"))
    )
    (net (code "92") (name "unconnected-(U1B-PD13-Pad82)") (class "Default")
      (node (ref "U1") (pin "82") (pinfunction "PD13_82") (pintype "bidirectional+no_connect"))
    )
    (net (code "93") (name "unconnected-(U1B-PD14-Pad85)") (class "Default")
      (node (ref "U1") (pin "85") (pinfunction "PD14_85") (pintype "bidirectional+no_connect"))
    )
    (net (code "94") (name "unconnected-(U1B-PD15-Pad86)") (class "Default")
      (node (ref "U1") (pin "86") (pinfunction "PD15_86") (pintype "bidirectional+no_connect"))
    )
    (net (code "95") (name "unconnected-(U1C-PE0-Pad141)") (class "Default")
      (node (ref "U1") (pin "141") (pinfunction "PE0_141") (pintype "bidirectional+no_connect"))
    )
    (net (code "96") (name "unconnected-(U1C-PE1-Pad142)") (class "Default")
      (node (ref "U1") (pin "142") (pinfunction "PE1_142") (pintype "bidirectional+no_connect"))
    )
    (net (code "97") (name "unconnected-(U1C-PE2-Pad1)") (class "Default")
      (node (ref "U1") (pin "1") (pinfunction "PE2_1") (pintype "bidirectional+no_connect"))
    )
    (net (code "98") (name "unconnected-(U1C-PE3-Pad2)") (class "Default")
      (node (ref "U1") (pin "2") (pinfunction "PE3_2") (pintype "bidirectional+no_connect"))
    )
    (net (code "99") (name "unconnected-(U1C-PE4-Pad3)") (class "Default")
      (node (ref "U1") (pin "3") (pinfunction "PE4_3") (pintype "bidirectional+no_connect"))
    )
    (net (code "100") (name "unconnected-(U1C-PE5-Pad4)") (class "Default")
      (node (ref "U1") (pin "4") (pinfunction "PE5_4") (pintype "bidirectional+no_connect"))
    )
    (net (code "101") (name "unconnected-(U1C-PE6-Pad5)") (class "Default")
      (node (ref "U1") (pin "5") (pinfunction "PE6_5") (pintype "bidirectional+no_connect"))
    )
    (net (code "102") (name "unconnected-(U1C-PE7-Pad58)") (class "Default")
      (node (ref "U1") (pin "58") (pinfunction "PE7_58") (pintype "bidirectional+no_connect"))
    )
    (net (code "103") (name "unconnected-(U1C-PE8-Pad59)") (class "Default")
      (node (ref "U1") (pin "59") (pinfunction "PE8_59") (pintype "bidirectional+no_connect"))
    )
    (net (code "104") (name "unconnected-(U1C-PE9-Pad60)") (class "Default")
      (node (ref "U1") (pin "60") (pinfunction "PE9_60") (pintype "bidirectional+no_connect"))
    )
    (net (code "105") (name "unconnected-(U1C-PE10-Pad63)") (class "Default")
      (node (ref "U1") (pin "63") (pinfunction "PE10_63") (pintype "bidirectional+no_connect"))
    )
    (net (code "106") (name "unconnected-(U1C-PE11-Pad64)") (class "Default")
      (node (ref "U1") (pin "64") (pinfunction "PE11_64") (pintype "bidirectional+no_connect"))
    )
    (net (code "107") (name "unconnected-(U1C-PE12-Pad65)") (class "Default")
      (node (ref "U1") (pin "65") (pinfunction "PE12_65") (pintype "bidirectional+no_connect"))
    )
    (net (code "108") (name "unconnected-(U1C-PE13-Pad66)") (class "Default")
      (node (ref "U1") (pin "66") (pinfunction "PE13_66") (pintype "bidirectional+no_connect"))
    )
    (net (code "109") (name "unconnected-(U1C-PE14-Pad67)") (class "Default")
      (node (ref "U1") (pin "67") (pinfunction "PE14_67") (pintype "bidirectional+no_connect"))
    )
    (net (code "110") (name "unconnected-(U1C-PE15-Pad68)") (class "Default")
      (node (ref "U1") (pin "68") (pinfunction "PE15_68") (pintype "bidirectional+no_connect"))
    )
    (net (code "111") (name "unconnected-(U1C-PF0-Pad10)") (class "Default")
      (node (ref "U1") (pin "10") (pinfunction "PF0_10") (pintype "bidirectional+no_connect"))
    )
    (net (code "112") (name "unconnected-(U1C-PF1-Pad11)") (class "Default")
      (node (ref "U1") (pin "11") (pinfunction "PF1_11") (pintype "bidirectional+no_connect"))
    )
    (net (code "113") (name "unconnected-(U1C-PF2-Pad12)") (class "Default")
      (node (ref "U1") (pin "12") (pinfunction "PF2_12") (pintype "bidirectional+no_connect"))
    )
    (net (code "114") (name "unconnected-(U1C-PF3-Pad13)") (class "Default")
      (node (ref "U1") (pin "13") (pinfunction "PF3_13") (pintype "bidirectional+no_connect"))
    )
    (net (code "115") (name "unconnected-(U1C-PF4-Pad14)") (class "Default")
      (node (ref "U1") (pin "14") (pinfunction "PF4_14") (pintype "bidirectional+no_connect"))
    )
    (net (code "116") (name "unconnected-(U1C-PF5-Pad15)") (class "Default")
      (node (ref "U1") (pin "15") (pinfunction "PF5_15") (pintype "bidirectional+no_connect"))
    )
    (net (code "117") (name "unconnected-(U1C-PF6-Pad18)") (class "Default")
      (node (ref "U1") (pin "18") (pinfunction "PF6_18") (pintype "bidirectional+no_connect"))
    )
    (net (code "118") (name "unconnected-(U1C-PF7-Pad19)") (class "Default")
      (node (ref "U1") (pin "19") (pinfunction "PF7_19") (pintype "bidirectional+no_connect"))
    )
    (net (code "119") (name "unconnected-(U1C-PF8-Pad20)") (class "Default")
      (node (ref "U1") (pin "20") (pinfunction "PF8_20") (pintype "bidirectional+no_connect"))
    )
    (net (code "120") (name "unconnected-(U1C-PF9-Pad21)") (class "Default")
      (node (ref "U1") (pin "21") (pinfunction "PF9_21") (pintype "bidirectional+no_connect"))
    )
    (net (code "121") (name "unconnected-(U1C-PF10-Pad22)") (class "Default")
      (node (ref "U1") (pin "22") (pinfunction "PF10_22") (pintype "bidirectional+no_connect"))
    )
    (net (code "122") (name "unconnected-(U1C-PF11-Pad49)") (class "Default")
      (node (ref "U1") (pin "49") (pinfunction "PF11_49") (pintype "bidirectional+no_connect"))
    )
    (net (code "123") (name "unconnected-(U1C-PF12-Pad50)") (class "Default")
      (node (ref "U1") (pin "50") (pinfunction "PF12_50") (pintype "bidirectional+no_connect"))
    )
    (net (code "124") (name "unconnected-(U1C-PF13-Pad53)") (class "Default")
      (node (ref "U1") (pin "53") (pinfunction "PF13_53") (pintype "bidirectional+no_connect"))
    )
    (net (code "125") (name "unconnected-(U1C-PF14-Pad54)") (class "Default")
      (node (ref "U1") (pin "54") (pinfunction "PF14_54") (pintype "bidirectional+no_connect"))
    )
    (net (code "126") (name "unconnected-(U1C-PF15-Pad55)") (class "Default")
      (node (ref "U1") (pin "55") (pinfunction "PF15_55") (pintype "bidirectional+no_connect"))
    )
    (net (code "127") (name "unconnected-(U1C-PG0-Pad56)") (class "Default")
      (node (ref "U1") (pin "56") (pinfunction "PG0_56") (pintype "bidirectional+no_connect"))
    )
    (net (code "128") (name "unconnected-(U1C-PG1-Pad57)") (class "Default")
      (node (ref "U1") (pin "57") (pinfunction "PG1_57") (pintype "bidirectional+no_connect"))
    )
    (net (code "129") (name "unconnected-(U1C-PG2-Pad87)") (class "Default")
      (node (ref "U1") (pin "87") (pinfunction "PG2_87") (pintype "bidirectional+no_connect"))
    )
    (net (code "130") (name "unconnected-(U1C-PG3-Pad88)") (class "Default")
      (node (ref "U1") (pin "88") (pinfunction "PG3_88") (pintype "bidirectional+no_connect"))
    )
    (net (code "131") (name "unconnected-(U1C-PG4-Pad89)") (class "Default")
      (node (ref "U1") (pin "89") (pinfunction "PG4_89") (pintype "bidirectional+no_connect"))
    )
    (net (code "132") (name "unconnected-(U1C-PG5-Pad90)") (class "Default")
      (node (ref "U1") (pin "90") (pinfunction "PG5_90") (pintype "bidirectional+no_connect"))
    )
    (net (code "133") (name "unconnected-(U1C-PG6-Pad91)") (class "Default")
      (node (ref "U1") (pin "91") (pinfunction "PG6_91") (pintype "bidirectional+no_connect"))
    )
    (net (code "134") (name "unconnected-(U1C-PG7-Pad92)") (class "Default")
      (node (ref "U1") (pin "92") (pinfunction "PG7_92") (pintype "bidirectional+no_connect"))
    )
    (net (code "135") (name "unconnected-(U1C-PG8-Pad93)") (class "Default")
      (node (ref "U1") (pin "93") (pinfunction "PG8_93") (pintype "bidirectional+no_connect"))
    )
    (net (code "136") (name "unconnected-(U1C-PG9-Pad124)") (class "Default")
      (node (ref "U1") (pin "124") (pinfunction "PG9_124") (pintype "bidirectional+no_connect"))
    )
    (net (code "137") (name "unconnected-(U1C-PG10-Pad125)") (class "Default")
      (node (ref "U1") (pin "125") (pinfunction "PG10_125") (pintype "bidirectional+no_connect"))
    )
    (net (code "138") (name "unconnected-(U1C-PG11-Pad126)") (class "Default")
      (node (ref "U1") (pin "126") (pinfunction "PG11_126") (pintype "bidirectional+no_connect"))
    )
    (net (code "139") (name "unconnected-(U1C-PG12-Pad127)") (class "Default")
      (node (ref "U1") (pin "127") (pinfunction "PG12_127") (pintype "bidirectional+no_connect"))
    )
    (net (code "140") (name "unconnected-(U1C-PG13-Pad128)") (class "Default")
      (node (ref "U1") (pin "128") (pinfunction "PG13_128") (pintype "bidirectional+no_connect"))
    )
    (net (code "141") (name "unconnected-(U1C-PG14-Pad129)") (class "Default")
      (node (ref "U1") (pin "129") (pinfunction "PG14_129") (pintype "bidirectional+no_connect"))
    )
    (net (code "142") (name "unconnected-(U1C-PG15-Pad132)") (class "Default")
      (node (ref "U1") (pin "132") (pinfunction "PG15_132") (pintype "bidirectional+no_connect"))
    )
    (net (code "143") (name "unconnected-(U3-SENSE-Pad2)") (class "Default")
      (node (ref "U3") (pin "2") (pinfunction "SENSE_2") (pintype "input+no_connect"))
    )
    (net (code "144") (name "unconnected-(U3-SHUTDOWN-Pad3)") (class "Default")
      (node (ref "U3") (pin "3") (pinfunction "SHUTDOWN_3") (pintype "input+no_connect"))
    )
    (net (code "145") (name "unconnected-(U3-VTAP-Pad6)") (class "Default")
      (node (ref "U3") (pin "6") (pinfunction "VTAP_6") (pintype "output+no_connect"))
    )
    (net (code "146") (name "unconnected-(U3-~{ERROR}-Pad5)") (class "Default")
      (node (ref "U3") (pin "5") (pinfunction "~{ERROR}_5") (pintype "output+no_connect"))
    )
    (net (code "147") (name "unconnected-(U4-2IN+-Pad5)") (class "Default")
      (node (ref "U4") (pin "5") (pinfunction "2IN+_5") (pintype "passive"))
    )
    (net (code "148") (name "unconnected-(U4-2IN--Pad6)") (class "Default")
      (node (ref "U4") (pin "6") (pinfunction "2IN-_6") (pintype "passive"))
    )
    (net (code "149") (name "unconnected-(U4-2OUT-Pad7)") (class "Default")
      (node (ref "U4") (pin "7") (pinfunction "2OUT_7") (pintype "passive"))
    )
    (net (code "150") (name "unconnected-(U4-3IN+-Pad12)") (class "Default")
      (node (ref "U4") (pin "12") (pinfunction "3IN+_12") (pintype "passive"))
    )
    (net (code "151") (name "unconnected-(U4-3IN--Pad13)") (class "Default")
      (node (ref "U4") (pin "13") (pinfunction "3IN-_13") (pintype "passive"))
    )
    (net (code "152") (name "unconnected-(U4-3OUT-Pad14)") (class "Default")
      (node (ref "U4") (pin "14") (pinfunction "3OUT_14") (pintype "passive"))
    )
    (net (code "153") (name "unconnected-(U4-4IN+-Pad10)") (class "Default")
      (node (ref "U4") (pin "10") (pinfunction "4IN+_10") (pintype "passive"))
    )
    (net (code "154") (name "unconnected-(U4-4IN--Pad9)") (class "Default")
      (node (ref "U4") (pin "9") (pinfunction "4IN-_9") (pintype "passive"))
    )
    (net (code "155") (name "unconnected-(U4-4OUT-Pad8)") (class "Default")
      (node (ref "U4") (pin "8") (pinfunction "4OUT_8") (pintype "passive"))
    )
    (net (code "156") (name "unconnected-(U5-CBUS0-Pad15)") (class "Default")
      (node (ref "U5") (pin "15") (pinfunction "CBUS0_15") (pintype "bidirectional+no_connect"))
    )
    (net (code "157") (name "unconnected-(U5-CBUS1-Pad14)") (class "Default")
      (node (ref "U5") (pin "14") (pinfunction "CBUS1_14") (pintype "bidirectional+no_connect"))
    )
    (net (code "158") (name "unconnected-(U5-CBUS2-Pad7)") (class "Default")
      (node (ref "U5") (pin "7") (pinfunction "CBUS2_7") (pintype "bidirectional+no_connect"))
    )
    (net (code "159") (name "unconnected-(U5-CBUS3-Pad16)") (class "Default")
      (node (ref "U5") (pin "16") (pinfunction "CBUS3_16") (pintype "bidirectional+no_connect"))
    )
    (net (code "160") (name "unconnected-(U5-~{CTS}-Pad6)") (class "Default")
      (node (ref "U5") (pin "6") (pinfunction "~{CTS}_6") (pintype "input+no_connect"))
    )
    (net (code "161") (name "unconnected-(U5-~{RTS}-Pad2)") (class "Default")
      (node (ref "U5") (pin "2") (pinfunction "~{RTS}_2") (pintype "input+no_connect"))
    )
  )
)
